# low_noise_amplifier_module.net
KiCad netlist of a schematic drawn in Altium Designer
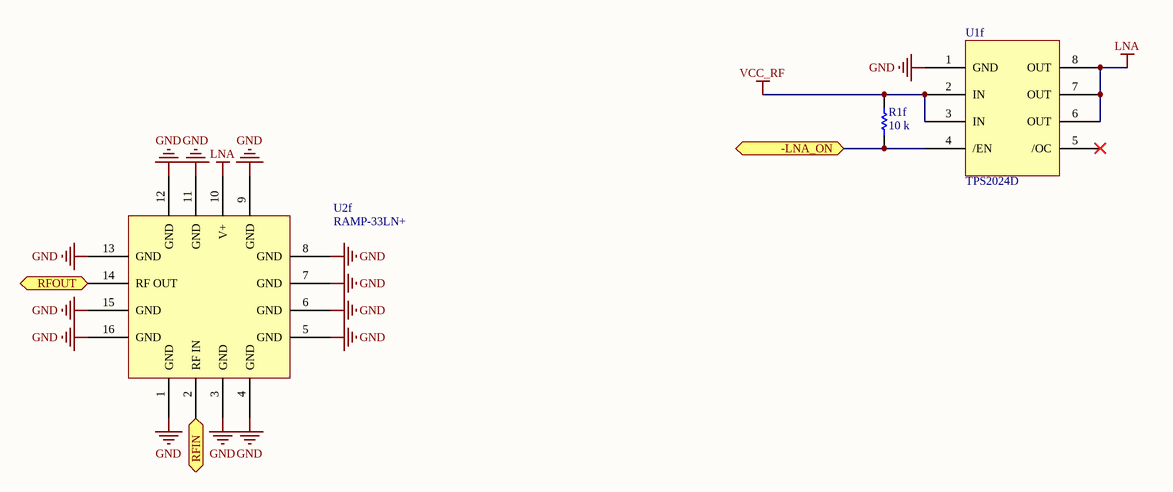
[diagram p0: low noise amplifier module.SchDoc]

(export (version "E")
  (design (tool "Eeschema 10.0.6"))
  (components
    (comp (ref "R1f")
      (value "10 k")
      (footprint "0603")
      (fields (field (name "PUBLISHER") "Altium Limited"))
      (libsource (lib "Miscellaneous Devices") (part "Res1"))
    )
    (comp (ref "U1f")
      (value "TPS2024D")
      (footprint "SO-8")
      (description "296-2564-5-ND")
      (libsource (lib "allspace_schem") (part "TPS2024"))
    )
    (comp (ref "U2f")
      (value "RAMP-33LN+")
      (footprint "CK605")
      (libsource (lib "allspace_schem") (part "RAMP-33LN+"))
    )
  )
  (nets
    (net (code "1") (name "/-LNA_ON") (class "Default")
      (node (ref "R1f") (pin "1") (pinfunction "1_1") (pintype "passive"))
      (node (ref "U1f") (pin "4") (pinfunction "/EN_4") (pintype "passive"))
    )
    (net (code "2") (name "/RFIN") (class "Default")
      (node (ref "U2f") (pin "2") (pinfunction "RF_IN_2") (pintype "passive"))
    )
    (net (code "3") (name "/RFOUT") (class "Default")
      (node (ref "U2f") (pin "14") (pinfunction "RF_OUT_14") (pintype "passive"))
    )
    (net (code "4") (name "GND") (class "Default")
      (node (ref "U1f") (pin "1") (pinfunction "GND_1") (pintype "passive"))
      (node (ref "U2f") (pin "1") (pinfunction "GND_1") (pintype "passive"))
      (node (ref "U2f") (pin "11") (pinfunction "GND_11") (pintype "passive"))
      (node (ref "U2f") (pin "12") (pinfunction "GND_12") (pintype "passive"))
      (node (ref "U2f") (pin "13") (pinfunction "GND_13") (pintype "passive"))
      (node (ref "U2f") (pin "15") (pinfunction "GND_15") (pintype "passive"))
      (node (ref "U2f") (pin "16") (pinfunction "GND_16") (pintype "passive"))
      (node (ref "U2f") (pin "3") (pinfunction "GND_3") (pintype "passive"))
      (node (ref "U2f") (pin "4") (pinfunction "GND_4") (pintype "passive"))
      (node (ref "U2f") (pin "5") (pinfunction "GND_5") (pintype "passive"))
      (node (ref "U2f") (pin "6") (pinfunction "GND_6") (pintype "passive"))
      (node (ref "U2f") (pin "7") (pinfunction "GND_7") (pintype "passive"))
      (node (ref "U2f") (pin "8") (pinfunction "GND_8") (pintype "passive"))
      (node (ref "U2f") (pin "9") (pinfunction "GND_9") (pintype "passive"))
    )
    (net (code "5") (name "LNA") (class "Default")
      (node (ref "U1f") (pin "6") (pinfunction "OUT_6") (pintype "passive"))
      (node (ref "U1f") (pin "7") (pinfunction "OUT_7") (pintype "passive"))
      (node (ref "U1f") (pin "8") (pinfunction "OUT_8") (pintype "passive"))
      (node (ref "U2f") (pin "10") (pinfunction "V+_10") (pintype "passive"))
    )
    (net (code "6") (name "VCC_RF") (class "Default")
      (node (ref "R1f") (pin "2") (pinfunction "2_2") (pintype "passive"))
      (node (ref "U1f") (pin "2") (pinfunction "IN_2") (pintype "passive"))
      (node (ref "U1f") (pin "3") (pinfunction "IN_3") (pintype "passive"))
    )
    (net (code "7") (name "unconnected-(U1f-{slash}OC-Pad5)") (class "Default")
      (node (ref "U1f") (pin "5") (pinfunction "/OC_5") (pintype "passive+no_connect"))
    )
  )
)
